# ALU_Logic.net
KiCad netlist of a schematic drawn in Altium Designer
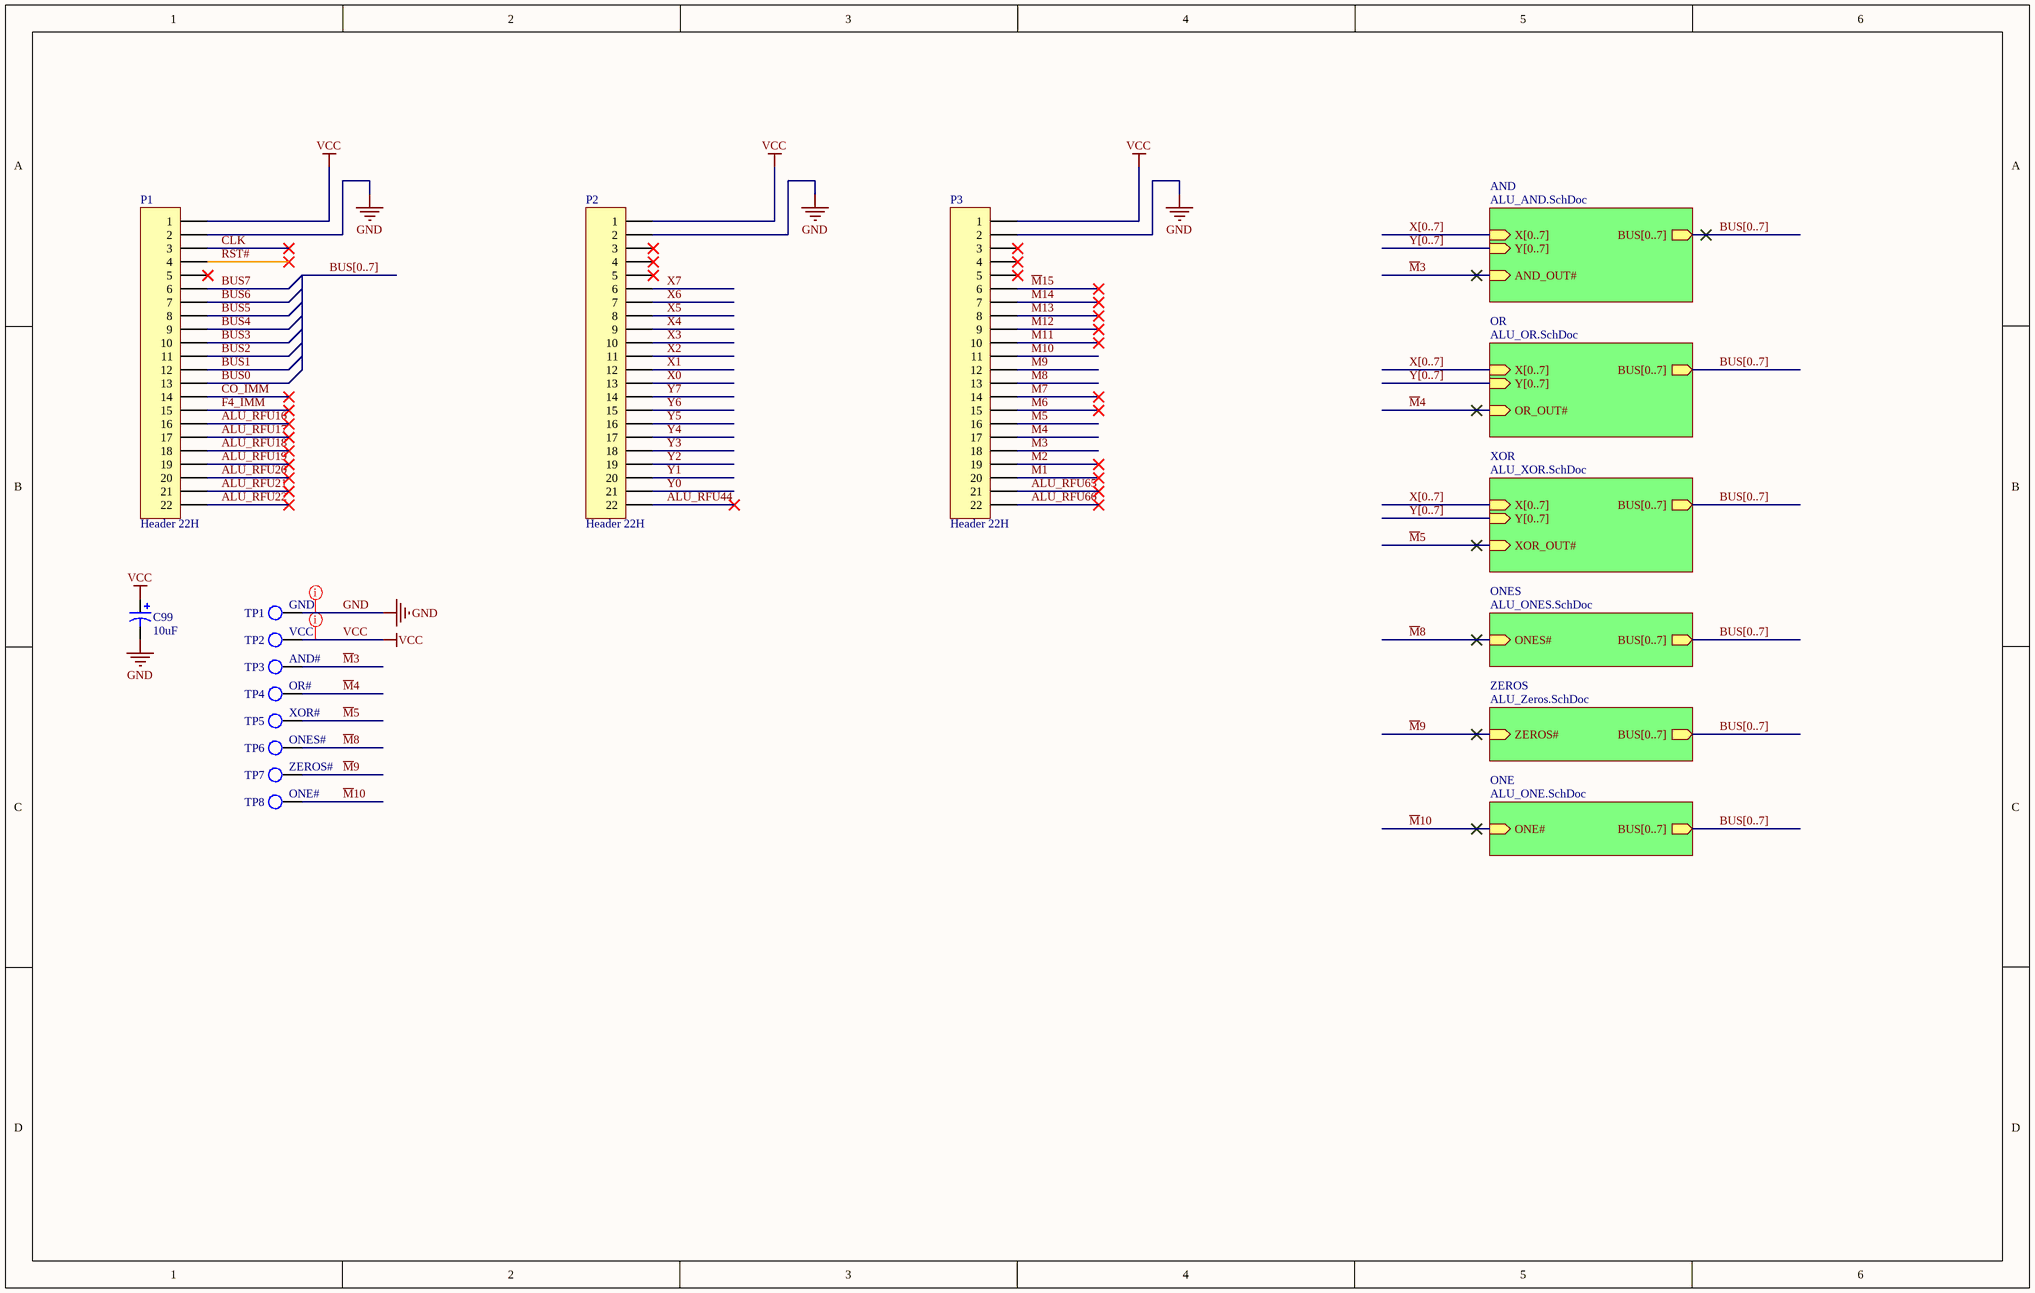
[diagram p0: ALU_Logic.SchDoc]

(export (version "E")
  (design (tool "Eeschema 10.0.6"))
  (components
    (comp (ref "C99")
      (value "10uF")
      (footprint "C5x7")
      (description "Polarized Capacitor")
      (fields (field (name "Comment") "Cap Pol5") (field (name "PUBLISHER") "Altium Limited"))
      (libsource (lib "Miscellaneous Devices") (part "Cap Pol5"))
    )
    (comp (ref "P1")
      (value "Header 22H")
      (footprint "HDR1X22H")
      (description "Header, 22-Pin, Right Angle")
      (fields (field (name "PUBLISHER") "Altium Limited"))
      (libsource (lib "Miscellaneous Connectors") (part "Header 22H"))
    )
    (comp (ref "P2")
      (value "Header 22H")
      (footprint "HDR1X22H")
      (description "Header, 22-Pin, Right Angle")
      (fields (field (name "PUBLISHER") "Altium Limited"))
      (libsource (lib "Miscellaneous Connectors") (part "Header 22H"))
    )
    (comp (ref "P3")
      (value "Header 22H")
      (footprint "HDR1X22H")
      (description "Header, 22-Pin, Right Angle")
      (fields (field (name "PUBLISHER") "Altium Limited"))
      (libsource (lib "Miscellaneous Connectors") (part "Header 22H"))
    )
    (comp (ref "TP1") (value "GND") (footprint "KSTN-5011_V") (libsource (lib "TP") (part "TP")))
    (comp (ref "TP2") (value "VCC") (footprint "KSTN-5011_V") (libsource (lib "TP") (part "TP")))
    (comp (ref "TP3") (value "AND#") (footprint "KSTN-5011_V") (libsource (lib "TP") (part "TP")))
    (comp (ref "TP4") (value "OR#") (footprint "KSTN-5011_V") (libsource (lib "TP") (part "TP")))
    (comp (ref "TP5") (value "XOR#") (footprint "KSTN-5011_V") (libsource (lib "TP") (part "TP")))
    (comp (ref "TP6") (value "ONES#") (footprint "KSTN-5011_V") (libsource (lib "TP") (part "TP")))
    (comp (ref "TP7") (value "ZEROS#") (footprint "KSTN-5011_V") (libsource (lib "TP") (part "TP")))
    (comp (ref "TP8") (value "ONE#") (footprint "KSTN-5011_V") (libsource (lib "TP") (part "TP")))
  )
  (nets
    (net (code "1") (name "/ALU_RFU16") (class "Default")
      (node (ref "P1") (pin "16") (pinfunction "16_16") (pintype "passive+no_connect"))
    )
    (net (code "2") (name "/ALU_RFU17") (class "Default")
      (node (ref "P1") (pin "17") (pinfunction "17_17") (pintype "passive+no_connect"))
    )
    (net (code "3") (name "/ALU_RFU18") (class "Default")
      (node (ref "P1") (pin "18") (pinfunction "18_18") (pintype "passive+no_connect"))
    )
    (net (code "4") (name "/ALU_RFU19") (class "Default")
      (node (ref "P1") (pin "19") (pinfunction "19_19") (pintype "passive+no_connect"))
    )
    (net (code "5") (name "/ALU_RFU20") (class "Default")
      (node (ref "P1") (pin "20") (pinfunction "20_20") (pintype "passive+no_connect"))
    )
    (net (code "6") (name "/ALU_RFU21") (class "Default")
      (node (ref "P1") (pin "21") (pinfunction "21_21") (pintype "passive+no_connect"))
    )
    (net (code "7") (name "/ALU_RFU22") (class "Default")
      (node (ref "P1") (pin "22") (pinfunction "22_22") (pintype "passive+no_connect"))
    )
    (net (code "8") (name "/ALU_RFU44") (class "Default")
      (node (ref "P2") (pin "22") (pinfunction "22_22") (pintype "passive+no_connect"))
    )
    (net (code "9") (name "/ALU_RFU65") (class "Default")
      (node (ref "P3") (pin "21") (pinfunction "21_21") (pintype "passive+no_connect"))
    )
    (net (code "10") (name "/ALU_RFU66") (class "Default")
      (node (ref "P3") (pin "22") (pinfunction "22_22") (pintype "passive+no_connect"))
    )
    (net (code "11") (name "/BUS0") (class "Default")
      (node (ref "P1") (pin "13") (pinfunction "13_13") (pintype "passive"))
    )
    (net (code "12") (name "/BUS1") (class "Default")
      (node (ref "P1") (pin "12") (pinfunction "12_12") (pintype "passive"))
    )
    (net (code "13") (name "/BUS2") (class "Default")
      (node (ref "P1") (pin "11") (pinfunction "11_11") (pintype "passive"))
    )
    (net (code "14") (name "/BUS3") (class "Default")
      (node (ref "P1") (pin "10") (pinfunction "10_10") (pintype "passive"))
    )
    (net (code "15") (name "/BUS4") (class "Default")
      (node (ref "P1") (pin "9") (pinfunction "9_9") (pintype "passive"))
    )
    (net (code "16") (name "/BUS5") (class "Default")
      (node (ref "P1") (pin "8") (pinfunction "8_8") (pintype "passive"))
    )
    (net (code "17") (name "/BUS6") (class "Default")
      (node (ref "P1") (pin "7") (pinfunction "7_7") (pintype "passive"))
    )
    (net (code "18") (name "/BUS7") (class "Default")
      (node (ref "P1") (pin "6") (pinfunction "6_6") (pintype "passive"))
    )
    (net (code "20") (name "/CLK") (class "Default")
      (node (ref "P1") (pin "3") (pinfunction "3_3") (pintype "passive+no_connect"))
    )
    (net (code "21") (name "/CO_IMM") (class "Default")
      (node (ref "P1") (pin "14") (pinfunction "14_14") (pintype "passive+no_connect"))
    )
    (net (code "22") (name "/F4_IMM") (class "Default")
      (node (ref "P1") (pin "15") (pinfunction "15_15") (pintype "passive+no_connect"))
    )
    (net (code "23") (name "/RST#") (class "Default")
      (node (ref "P1") (pin "4") (pinfunction "4_4") (pintype "passive+no_connect"))
    )
    (net (code "24") (name "/X0") (class "Default")
      (node (ref "P2") (pin "13") (pinfunction "13_13") (pintype "passive"))
    )
    (net (code "25") (name "/X1") (class "Default")
      (node (ref "P2") (pin "12") (pinfunction "12_12") (pintype "passive"))
    )
    (net (code "26") (name "/X2") (class "Default")
      (node (ref "P2") (pin "11") (pinfunction "11_11") (pintype "passive"))
    )
    (net (code "27") (name "/X3") (class "Default")
      (node (ref "P2") (pin "10") (pinfunction "10_10") (pintype "passive"))
    )
    (net (code "28") (name "/X4") (class "Default")
      (node (ref "P2") (pin "9") (pinfunction "9_9") (pintype "passive"))
    )
    (net (code "29") (name "/X5") (class "Default")
      (node (ref "P2") (pin "8") (pinfunction "8_8") (pintype "passive"))
    )
    (net (code "30") (name "/X6") (class "Default")
      (node (ref "P2") (pin "7") (pinfunction "7_7") (pintype "passive"))
    )
    (net (code "31") (name "/X7") (class "Default")
      (node (ref "P2") (pin "6") (pinfunction "6_6") (pintype "passive"))
    )
    (net (code "33") (name "/Y0") (class "Default")
      (node (ref "P2") (pin "21") (pinfunction "21_21") (pintype "passive"))
    )
    (net (code "34") (name "/Y1") (class "Default")
      (node (ref "P2") (pin "20") (pinfunction "20_20") (pintype "passive"))
    )
    (net (code "35") (name "/Y2") (class "Default")
      (node (ref "P2") (pin "19") (pinfunction "19_19") (pintype "passive"))
    )
    (net (code "36") (name "/Y3") (class "Default")
      (node (ref "P2") (pin "18") (pinfunction "18_18") (pintype "passive"))
    )
    (net (code "37") (name "/Y4") (class "Default")
      (node (ref "P2") (pin "17") (pinfunction "17_17") (pintype "passive"))
    )
    (net (code "38") (name "/Y5") (class "Default")
      (node (ref "P2") (pin "16") (pinfunction "16_16") (pintype "passive"))
    )
    (net (code "39") (name "/Y6") (class "Default")
      (node (ref "P2") (pin "15") (pinfunction "15_15") (pintype "passive"))
    )
    (net (code "40") (name "/Y7") (class "Default")
      (node (ref "P2") (pin "14") (pinfunction "14_14") (pintype "passive"))
    )
    (net (code "42") (name "/~{M}1") (class "Default")
      (node (ref "P3") (pin "20") (pinfunction "20_20") (pintype "passive+no_connect"))
    )
    (net (code "43") (name "/~{M}2") (class "Default")
      (node (ref "P3") (pin "19") (pinfunction "19_19") (pintype "passive+no_connect"))
    )
    (net (code "44") (name "/~{M}3") (class "Default")
      (node (ref "P3") (pin "18") (pinfunction "18_18") (pintype "passive"))
      (node (ref "TP3") (pin "1") (pintype "passive"))
    )
    (net (code "45") (name "/~{M}4") (class "Default")
      (node (ref "P3") (pin "17") (pinfunction "17_17") (pintype "passive"))
      (node (ref "TP4") (pin "1") (pintype "passive"))
    )
    (net (code "46") (name "/~{M}5") (class "Default")
      (node (ref "P3") (pin "16") (pinfunction "16_16") (pintype "passive"))
      (node (ref "TP5") (pin "1") (pintype "passive"))
    )
    (net (code "47") (name "/~{M}6") (class "Default")
      (node (ref "P3") (pin "15") (pinfunction "15_15") (pintype "passive+no_connect"))
    )
    (net (code "48") (name "/~{M}7") (class "Default")
      (node (ref "P3") (pin "14") (pinfunction "14_14") (pintype "passive+no_connect"))
    )
    (net (code "49") (name "/~{M}8") (class "Default")
      (node (ref "P3") (pin "13") (pinfunction "13_13") (pintype "passive"))
      (node (ref "TP6") (pin "1") (pintype "passive"))
    )
    (net (code "50") (name "/~{M}9") (class "Default")
      (node (ref "P3") (pin "12") (pinfunction "12_12") (pintype "passive"))
      (node (ref "TP7") (pin "1") (pintype "passive"))
    )
    (net (code "51") (name "/~{M}10") (class "Default")
      (node (ref "P3") (pin "11") (pinfunction "11_11") (pintype "passive"))
      (node (ref "TP8") (pin "1") (pintype "passive"))
    )
    (net (code "52") (name "/~{M}11") (class "Default")
      (node (ref "P3") (pin "10") (pinfunction "10_10") (pintype "passive+no_connect"))
    )
    (net (code "53") (name "/~{M}12") (class "Default")
      (node (ref "P3") (pin "9") (pinfunction "9_9") (pintype "passive+no_connect"))
    )
    (net (code "54") (name "/~{M}13") (class "Default")
      (node (ref "P3") (pin "8") (pinfunction "8_8") (pintype "passive+no_connect"))
    )
    (net (code "55") (name "/~{M}14") (class "Default")
      (node (ref "P3") (pin "7") (pinfunction "7_7") (pintype "passive+no_connect"))
    )
    (net (code "56") (name "/~{M}15") (class "Default")
      (node (ref "P3") (pin "6") (pinfunction "6_6") (pintype "passive+no_connect"))
    )
    (net (code "57") (name "GND") (class "Default")
      (node (ref "C99") (pin "2") (pinfunction "2_2") (pintype "passive"))
      (node (ref "P1") (pin "2") (pinfunction "2_2") (pintype "passive"))
      (node (ref "P2") (pin "2") (pinfunction "2_2") (pintype "passive"))
      (node (ref "P3") (pin "2") (pinfunction "2_2") (pintype "passive"))
      (node (ref "TP1") (pin "1") (pintype "passive"))
    )
    (net (code "58") (name "VCC") (class "Default")
      (node (ref "C99") (pin "1") (pinfunction "1_1") (pintype "passive"))
      (node (ref "P1") (pin "1") (pinfunction "1_1") (pintype "passive"))
      (node (ref "P2") (pin "1") (pinfunction "1_1") (pintype "passive"))
      (node (ref "P3") (pin "1") (pinfunction "1_1") (pintype "passive"))
      (node (ref "TP2") (pin "1") (pintype "passive"))
    )
    (net (code "59") (name "unconnected-(P1-Pad5)") (class "Default")
      (node (ref "P1") (pin "5") (pinfunction "5_5") (pintype "passive+no_connect"))
    )
    (net (code "60") (name "unconnected-(P2-Pad3)") (class "Default")
      (node (ref "P2") (pin "3") (pinfunction "3_3") (pintype "passive+no_connect"))
    )
    (net (code "61") (name "unconnected-(P2-Pad4)") (class "Default")
      (node (ref "P2") (pin "4") (pinfunction "4_4") (pintype "passive+no_connect"))
    )
    (net (code "62") (name "unconnected-(P2-Pad5)") (class "Default")
      (node (ref "P2") (pin "5") (pinfunction "5_5") (pintype "passive+no_connect"))
    )
    (net (code "63") (name "unconnected-(P3-Pad3)") (class "Default")
      (node (ref "P3") (pin "3") (pinfunction "3_3") (pintype "passive+no_connect"))
    )
    (net (code "64") (name "unconnected-(P3-Pad4)") (class "Default")
      (node (ref "P3") (pin "4") (pinfunction "4_4") (pintype "passive+no_connect"))
    )
    (net (code "65") (name "unconnected-(P3-Pad5)") (class "Default")
      (node (ref "P3") (pin "5") (pinfunction "5_5") (pintype "passive+no_connect"))
    )
  )
)
